# acelerometro.net
KiCad netlist of a schematic drawn in Altium Designer
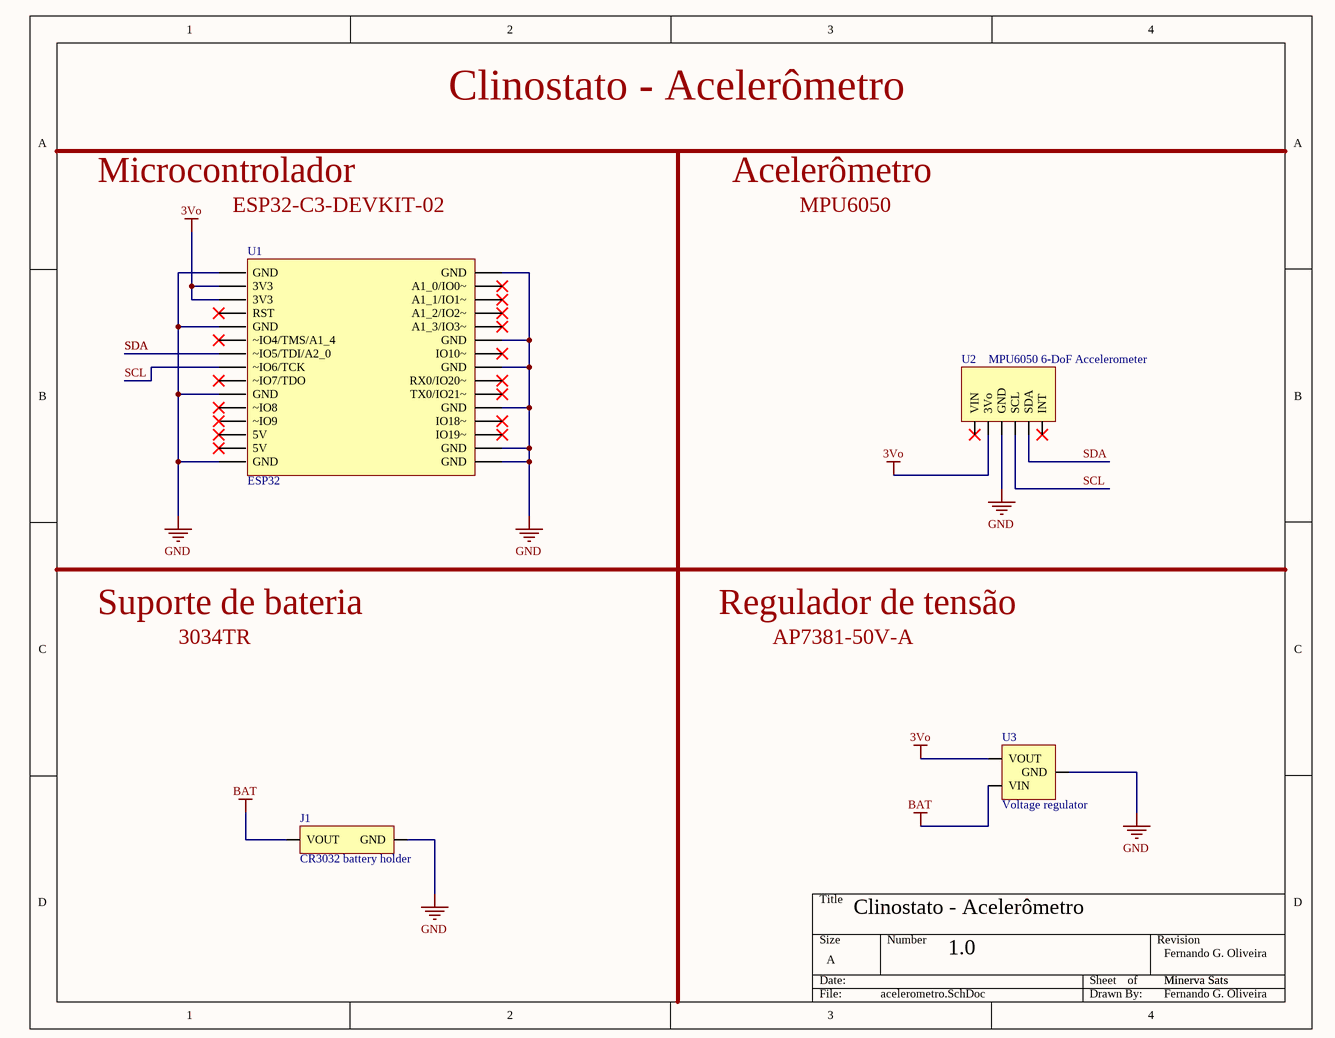
[diagram p0: acelerometro.SchDoc, right]

(export (version "E")
  (design (tool "Eeschema 10.0.6"))
  (components
    (comp (ref "J1")
      (value "CR3032 battery holder")
      (footprint "FP-3034TR-MFG")
      (libsource (lib "acelerometro") (part "3034TR"))
    )
    (comp (ref "U1")
      (value "ESP32")
      (footprint "FP-ESP32-C3-DevKitC-02-MFG")
      (fields
        (field (name "MANUFACTURER") "Espressif Systems")
        (field (name "MANUFACTURER PART NUMBER") "ESP32-C3-DEVKITC-02")
      )
      (libsource (lib "Midas") (part "ESP32-C3-DEVKITC-02"))
    )
    (comp (ref "U2")
      (value "MPU6050 6-DoF Accelerometer")
      (footprint "MPU6050")
      (description "Apex Tool Group Ratcheting Tap and Die Set (40-Piece) 3886")
      (fields
        (field (name "MANUFACTURER") "Adafruit Industries")
        (field (name "MANUFACTURER PART NUMBER") "3886")
      )
      (libsource (lib "acelerometro") (part "3886"))
    )
    (comp (ref "U3")
      (value "Voltage regulator")
      (footprint "AP7381-50V-A")
      (description "Fixed Positive LDO Regulator")
      (fields (field (name "MANUFACTURER") "Diodes") (field (name "MANUFACTURER PART NUMBER") "AP7381-50V-A"))
      (libsource (lib "Schlib1") (part "AP7381-50V-A"))
    )
  )
  (nets
    (net (code "1") (name "/SCL") (class "Default")
      (node (ref "U1") (pin "8") (pinfunction "~IO6/TCK_8") (pintype "passive"))
      (node (ref "U2") (pin "4") (pinfunction "SCL_4") (pintype "passive"))
    )
    (net (code "2") (name "/SDA") (class "Default")
      (node (ref "U1") (pin "7") (pinfunction "~IO5/TDI/A2_0_7") (pintype "passive"))
      (node (ref "U2") (pin "5") (pinfunction "SDA_5") (pintype "passive"))
    )
    (net (code "3") (name "3Vo") (class "Default")
      (node (ref "U1") (pin "2") (pinfunction "3V3_2") (pintype "passive"))
      (node (ref "U1") (pin "3") (pinfunction "3V3_3") (pintype "passive"))
      (node (ref "U2") (pin "2") (pinfunction "3Vo_2") (pintype "passive"))
      (node (ref "U3") (pin "1") (pinfunction "VOUT_1") (pintype "passive"))
    )
    (net (code "4") (name "BAT") (class "Default")
      (node (ref "J1") (pin "1") (pinfunction "VOUT_1") (pintype "passive"))
      (node (ref "U3") (pin "3") (pinfunction "VIN_3") (pintype "passive"))
    )
    (net (code "5") (name "GND") (class "Default")
      (node (ref "J1") (pin "2") (pinfunction "GND_2") (pintype "passive"))
      (node (ref "U1") (pin "1") (pinfunction "GND_1") (pintype "passive"))
      (node (ref "U1") (pin "10") (pinfunction "GND_10") (pintype "passive"))
      (node (ref "U1") (pin "15") (pinfunction "GND_15") (pintype "passive"))
      (node (ref "U1") (pin "16") (pinfunction "GND_16") (pintype "passive"))
      (node (ref "U1") (pin "17") (pinfunction "GND_17") (pintype "passive"))
      (node (ref "U1") (pin "20") (pinfunction "GND_20") (pintype "passive"))
      (node (ref "U1") (pin "23") (pinfunction "GND_23") (pintype "passive"))
      (node (ref "U1") (pin "25") (pinfunction "GND_25") (pintype "passive"))
      (node (ref "U1") (pin "30") (pinfunction "GND_30") (pintype "passive"))
      (node (ref "U1") (pin "5") (pinfunction "GND_5") (pintype "passive"))
      (node (ref "U2") (pin "3") (pinfunction "GND_3") (pintype "passive"))
      (node (ref "U3") (pin "2") (pinfunction "GND_2") (pintype "passive"))
    )
    (net (code "6") (name "unconnected-(U1-5V-Pad13)") (class "Default")
      (node (ref "U1") (pin "13") (pinfunction "5V_13") (pintype "passive+no_connect"))
    )
    (net (code "7") (name "unconnected-(U1-5V-Pad14)") (class "Default")
      (node (ref "U1") (pin "14") (pinfunction "5V_14") (pintype "passive+no_connect"))
    )
    (net (code "8") (name "unconnected-(U1-A1_0{slash}IO0~-Pad29)") (class "Default")
      (node (ref "U1") (pin "29") (pinfunction "A1_0/IO0~_29") (pintype "passive+no_connect"))
    )
    (net (code "9") (name "unconnected-(U1-A1_1{slash}IO1~-Pad28)") (class "Default")
      (node (ref "U1") (pin "28") (pinfunction "A1_1/IO1~_28") (pintype "passive+no_connect"))
    )
    (net (code "10") (name "unconnected-(U1-A1_2{slash}IO2~-Pad27)") (class "Default")
      (node (ref "U1") (pin "27") (pinfunction "A1_2/IO2~_27") (pintype "passive+no_connect"))
    )
    (net (code "11") (name "unconnected-(U1-A1_3{slash}IO3~-Pad26)") (class "Default")
      (node (ref "U1") (pin "26") (pinfunction "A1_3/IO3~_26") (pintype "passive+no_connect"))
    )
    (net (code "12") (name "unconnected-(U1-IO10~-Pad24)") (class "Default")
      (node (ref "U1") (pin "24") (pinfunction "IO10~_24") (pintype "passive+no_connect"))
    )
    (net (code "13") (name "unconnected-(U1-IO18~-Pad19)") (class "Default")
      (node (ref "U1") (pin "19") (pinfunction "IO18~_19") (pintype "passive+no_connect"))
    )
    (net (code "14") (name "unconnected-(U1-IO19~-Pad18)") (class "Default")
      (node (ref "U1") (pin "18") (pinfunction "IO19~_18") (pintype "passive+no_connect"))
    )
    (net (code "15") (name "unconnected-(U1-RST-Pad4)") (class "Default")
      (node (ref "U1") (pin "4") (pinfunction "RST_4") (pintype "passive+no_connect"))
    )
    (net (code "16") (name "unconnected-(U1-RX0{slash}IO20~-Pad22)") (class "Default")
      (node (ref "U1") (pin "22") (pinfunction "RX0/IO20~_22") (pintype "passive+no_connect"))
    )
    (net (code "17") (name "unconnected-(U1-TX0{slash}IO21~-Pad21)") (class "Default")
      (node (ref "U1") (pin "21") (pinfunction "TX0/IO21~_21") (pintype "passive+no_connect"))
    )
    (net (code "18") (name "unconnected-(U1-~IO4{slash}TMS{slash}A1_4-Pad6)") (class "Default")
      (node (ref "U1") (pin "6") (pinfunction "~IO4/TMS/A1_4_6") (pintype "passive+no_connect"))
    )
    (net (code "19") (name "unconnected-(U1-~IO7{slash}TDO-Pad9)") (class "Default")
      (node (ref "U1") (pin "9") (pinfunction "~IO7/TDO_9") (pintype "passive+no_connect"))
    )
    (net (code "20") (name "unconnected-(U1-~IO8-Pad11)") (class "Default")
      (node (ref "U1") (pin "11") (pinfunction "~IO8_11") (pintype "passive+no_connect"))
    )
    (net (code "21") (name "unconnected-(U1-~IO9-Pad12)") (class "Default")
      (node (ref "U1") (pin "12") (pinfunction "~IO9_12") (pintype "passive+no_connect"))
    )
    (net (code "22") (name "unconnected-(U2-INT-Pad6)") (class "Default")
      (node (ref "U2") (pin "6") (pinfunction "INT_6") (pintype "passive+no_connect"))
    )
    (net (code "23") (name "unconnected-(U2-VIN-Pad1)") (class "Default")
      (node (ref "U2") (pin "1") (pinfunction "VIN_1") (pintype "passive+no_connect"))
    )
  )
)
